# ISensor_V2_1_sch.net
KiCad netlist of a schematic drawn in EAGLE
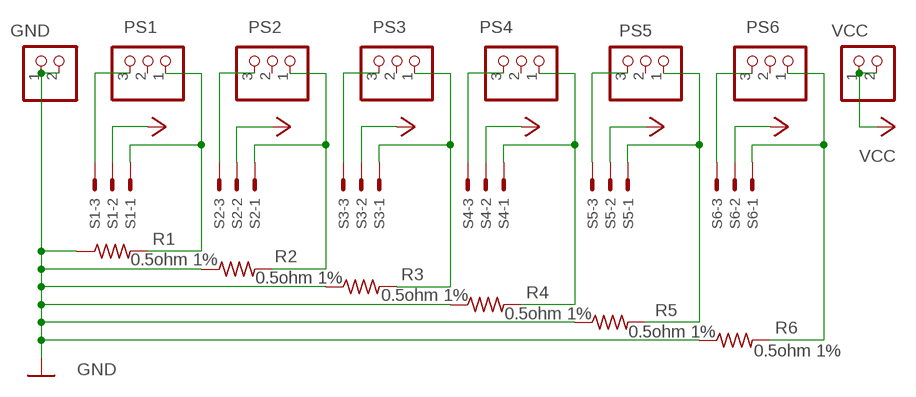
[diagram p0: schematic, sheet 1]

(export (version "E")
  (design (tool "Eeschema 10.0.6"))
  (components
    (comp (ref "GND")
      (value "PINHD-1X2")
      (footprint "eagle-import:1X02")
      (libsource (lib "eagle-import") (part "PINHD-1X2"))
    )
    (comp (ref "PS1")
      (value "PINHD-1X3")
      (footprint "eagle-import:1X03")
      (libsource (lib "eagle-import") (part "PINHD-1X3"))
    )
    (comp (ref "PS2")
      (value "PINHD-1X3")
      (footprint "eagle-import:1X03")
      (libsource (lib "eagle-import") (part "PINHD-1X3"))
    )
    (comp (ref "PS3")
      (value "PINHD-1X3")
      (footprint "eagle-import:1X03")
      (libsource (lib "eagle-import") (part "PINHD-1X3"))
    )
    (comp (ref "PS4")
      (value "PINHD-1X3")
      (footprint "eagle-import:1X03")
      (libsource (lib "eagle-import") (part "PINHD-1X3"))
    )
    (comp (ref "PS5")
      (value "PINHD-1X3")
      (footprint "eagle-import:1X03")
      (libsource (lib "eagle-import") (part "PINHD-1X3"))
    )
    (comp (ref "PS6")
      (value "PINHD-1X3")
      (footprint "eagle-import:1X03")
      (libsource (lib "eagle-import") (part "PINHD-1X3"))
    )
    (comp (ref "R1")
      (value "0.5ohm 1%")
      (footprint "eagle-import:R2512")
      (libsource (lib "eagle-import") (part "R-US_R2512"))
    )
    (comp (ref "R2")
      (value "0.5ohm 1%")
      (footprint "eagle-import:R2512")
      (libsource (lib "eagle-import") (part "R-US_R2512"))
    )
    (comp (ref "R3")
      (value "0.5ohm 1%")
      (footprint "eagle-import:R2512")
      (libsource (lib "eagle-import") (part "R-US_R2512"))
    )
    (comp (ref "R4")
      (value "0.5ohm 1%")
      (footprint "eagle-import:R2512")
      (libsource (lib "eagle-import") (part "R-US_R2512"))
    )
    (comp (ref "R5")
      (value "0.5ohm 1%")
      (footprint "eagle-import:R2512")
      (libsource (lib "eagle-import") (part "R-US_R2512"))
    )
    (comp (ref "R6")
      (value "0.5ohm 1%")
      (footprint "eagle-import:R2512")
      (libsource (lib "eagle-import") (part "R-US_R2512"))
    )
    (comp (ref "S1")
      (value "22-27-2031-03")
      (footprint "eagle-import:6410-03")
      (libsource (lib "eagle-import") (part "22-?-0327-2031"))
    )
    (comp (ref "S2")
      (value "22-27-2031-03")
      (footprint "eagle-import:6410-03")
      (libsource (lib "eagle-import") (part "22-?-0327-2031"))
    )
    (comp (ref "S3")
      (value "22-27-2031-03")
      (footprint "eagle-import:6410-03")
      (libsource (lib "eagle-import") (part "22-?-0327-2031"))
    )
    (comp (ref "S4")
      (value "22-27-2031-03")
      (footprint "eagle-import:6410-03")
      (libsource (lib "eagle-import") (part "22-?-0327-2031"))
    )
    (comp (ref "S5")
      (value "22-27-2031-03")
      (footprint "eagle-import:6410-03")
      (libsource (lib "eagle-import") (part "22-?-0327-2031"))
    )
    (comp (ref "S6")
      (value "22-27-2031-03")
      (footprint "eagle-import:6410-03")
      (libsource (lib "eagle-import") (part "22-?-0327-2031"))
    )
    (comp (ref "VCC")
      (value "PINHD-1X2")
      (footprint "eagle-import:1X02")
      (libsource (lib "eagle-import") (part "PINHD-1X2"))
    )
  )
  (nets
    (net (code "1") (name "GND") (class "Default")
      (node (ref "GND") (pin "1") (pinfunction "1_1") (pintype "passive"))
      (node (ref "GND") (pin "2") (pinfunction "2_2") (pintype "passive"))
      (node (ref "R1") (pin "1") (pinfunction "1_1") (pintype "passive"))
      (node (ref "R2") (pin "1") (pinfunction "1_1") (pintype "passive"))
      (node (ref "R3") (pin "1") (pinfunction "1_1") (pintype "passive"))
      (node (ref "R4") (pin "1") (pinfunction "1_1") (pintype "passive"))
      (node (ref "R5") (pin "1") (pinfunction "1_1") (pintype "passive"))
      (node (ref "R6") (pin "1") (pinfunction "1_1") (pintype "passive"))
    )
    (net (code "2") (name "Net-(S1A-S)") (class "Default")
      (node (ref "PS1") (pin "1") (pinfunction "1_1") (pintype "passive"))
      (node (ref "R1") (pin "2") (pinfunction "2_2") (pintype "passive"))
      (node (ref "S1") (pin "1") (pinfunction "S_1") (pintype "passive"))
    )
    (net (code "3") (name "Net-(S1C-S)") (class "Default")
      (node (ref "PS1") (pin "3") (pinfunction "3_3") (pintype "passive"))
      (node (ref "S1") (pin "3") (pinfunction "S_3") (pintype "passive"))
    )
    (net (code "4") (name "Net-(S2A-S)") (class "Default")
      (node (ref "PS2") (pin "1") (pinfunction "1_1") (pintype "passive"))
      (node (ref "R2") (pin "2") (pinfunction "2_2") (pintype "passive"))
      (node (ref "S2") (pin "1") (pinfunction "S_1") (pintype "passive"))
    )
    (net (code "5") (name "Net-(S2C-S)") (class "Default")
      (node (ref "PS2") (pin "3") (pinfunction "3_3") (pintype "passive"))
      (node (ref "S2") (pin "3") (pinfunction "S_3") (pintype "passive"))
    )
    (net (code "6") (name "Net-(S3A-S)") (class "Default")
      (node (ref "PS3") (pin "1") (pinfunction "1_1") (pintype "passive"))
      (node (ref "R3") (pin "2") (pinfunction "2_2") (pintype "passive"))
      (node (ref "S3") (pin "1") (pinfunction "S_1") (pintype "passive"))
    )
    (net (code "7") (name "Net-(S3C-S)") (class "Default")
      (node (ref "PS3") (pin "3") (pinfunction "3_3") (pintype "passive"))
      (node (ref "S3") (pin "3") (pinfunction "S_3") (pintype "passive"))
    )
    (net (code "8") (name "Net-(S4A-S)") (class "Default")
      (node (ref "PS4") (pin "1") (pinfunction "1_1") (pintype "passive"))
      (node (ref "R4") (pin "2") (pinfunction "2_2") (pintype "passive"))
      (node (ref "S4") (pin "1") (pinfunction "S_1") (pintype "passive"))
    )
    (net (code "9") (name "Net-(S4C-S)") (class "Default")
      (node (ref "PS4") (pin "3") (pinfunction "3_3") (pintype "passive"))
      (node (ref "S4") (pin "3") (pinfunction "S_3") (pintype "passive"))
    )
    (net (code "10") (name "Net-(S5A-S)") (class "Default")
      (node (ref "PS5") (pin "1") (pinfunction "1_1") (pintype "passive"))
      (node (ref "R5") (pin "2") (pinfunction "2_2") (pintype "passive"))
      (node (ref "S5") (pin "1") (pinfunction "S_1") (pintype "passive"))
    )
    (net (code "11") (name "Net-(S5C-S)") (class "Default")
      (node (ref "PS5") (pin "3") (pinfunction "3_3") (pintype "passive"))
      (node (ref "S5") (pin "3") (pinfunction "S_3") (pintype "passive"))
    )
    (net (code "12") (name "Net-(S6A-S)") (class "Default")
      (node (ref "PS6") (pin "1") (pinfunction "1_1") (pintype "passive"))
      (node (ref "R6") (pin "2") (pinfunction "2_2") (pintype "passive"))
      (node (ref "S6") (pin "1") (pinfunction "S_1") (pintype "passive"))
    )
    (net (code "13") (name "Net-(S6C-S)") (class "Default")
      (node (ref "PS6") (pin "3") (pinfunction "3_3") (pintype "passive"))
      (node (ref "S6") (pin "3") (pinfunction "S_3") (pintype "passive"))
    )
    (net (code "14") (name "VCC") (class "Default")
      (node (ref "S1") (pin "2") (pinfunction "S_2") (pintype "passive"))
      (node (ref "S2") (pin "2") (pinfunction "S_2") (pintype "passive"))
      (node (ref "S3") (pin "2") (pinfunction "S_2") (pintype "passive"))
      (node (ref "S4") (pin "2") (pinfunction "S_2") (pintype "passive"))
      (node (ref "S5") (pin "2") (pinfunction "S_2") (pintype "passive"))
      (node (ref "S6") (pin "2") (pinfunction "S_2") (pintype "passive"))
      (node (ref "VCC") (pin "1") (pinfunction "1_1") (pintype "passive"))
      (node (ref "VCC") (pin "2") (pinfunction "2_2") (pintype "passive"))
    )
    (net (code "15") (name "unconnected-(PS1-Pad2)") (class "Default")
      (node (ref "PS1") (pin "2") (pinfunction "2_2") (pintype "passive"))
    )
    (net (code "16") (name "unconnected-(PS2-Pad2)") (class "Default")
      (node (ref "PS2") (pin "2") (pinfunction "2_2") (pintype "passive"))
    )
    (net (code "17") (name "unconnected-(PS3-Pad2)") (class "Default")
      (node (ref "PS3") (pin "2") (pinfunction "2_2") (pintype "passive"))
    )
    (net (code "18") (name "unconnected-(PS4-Pad2)") (class "Default")
      (node (ref "PS4") (pin "2") (pinfunction "2_2") (pintype "passive"))
    )
    (net (code "19") (name "unconnected-(PS5-Pad2)") (class "Default")
      (node (ref "PS5") (pin "2") (pinfunction "2_2") (pintype "passive"))
    )
    (net (code "20") (name "unconnected-(PS6-Pad2)") (class "Default")
      (node (ref "PS6") (pin "2") (pinfunction "2_2") (pintype "passive"))
    )
  )
)
